# 5min_DIP.net
KiCad netlist of a schematic drawn in Altium Designer
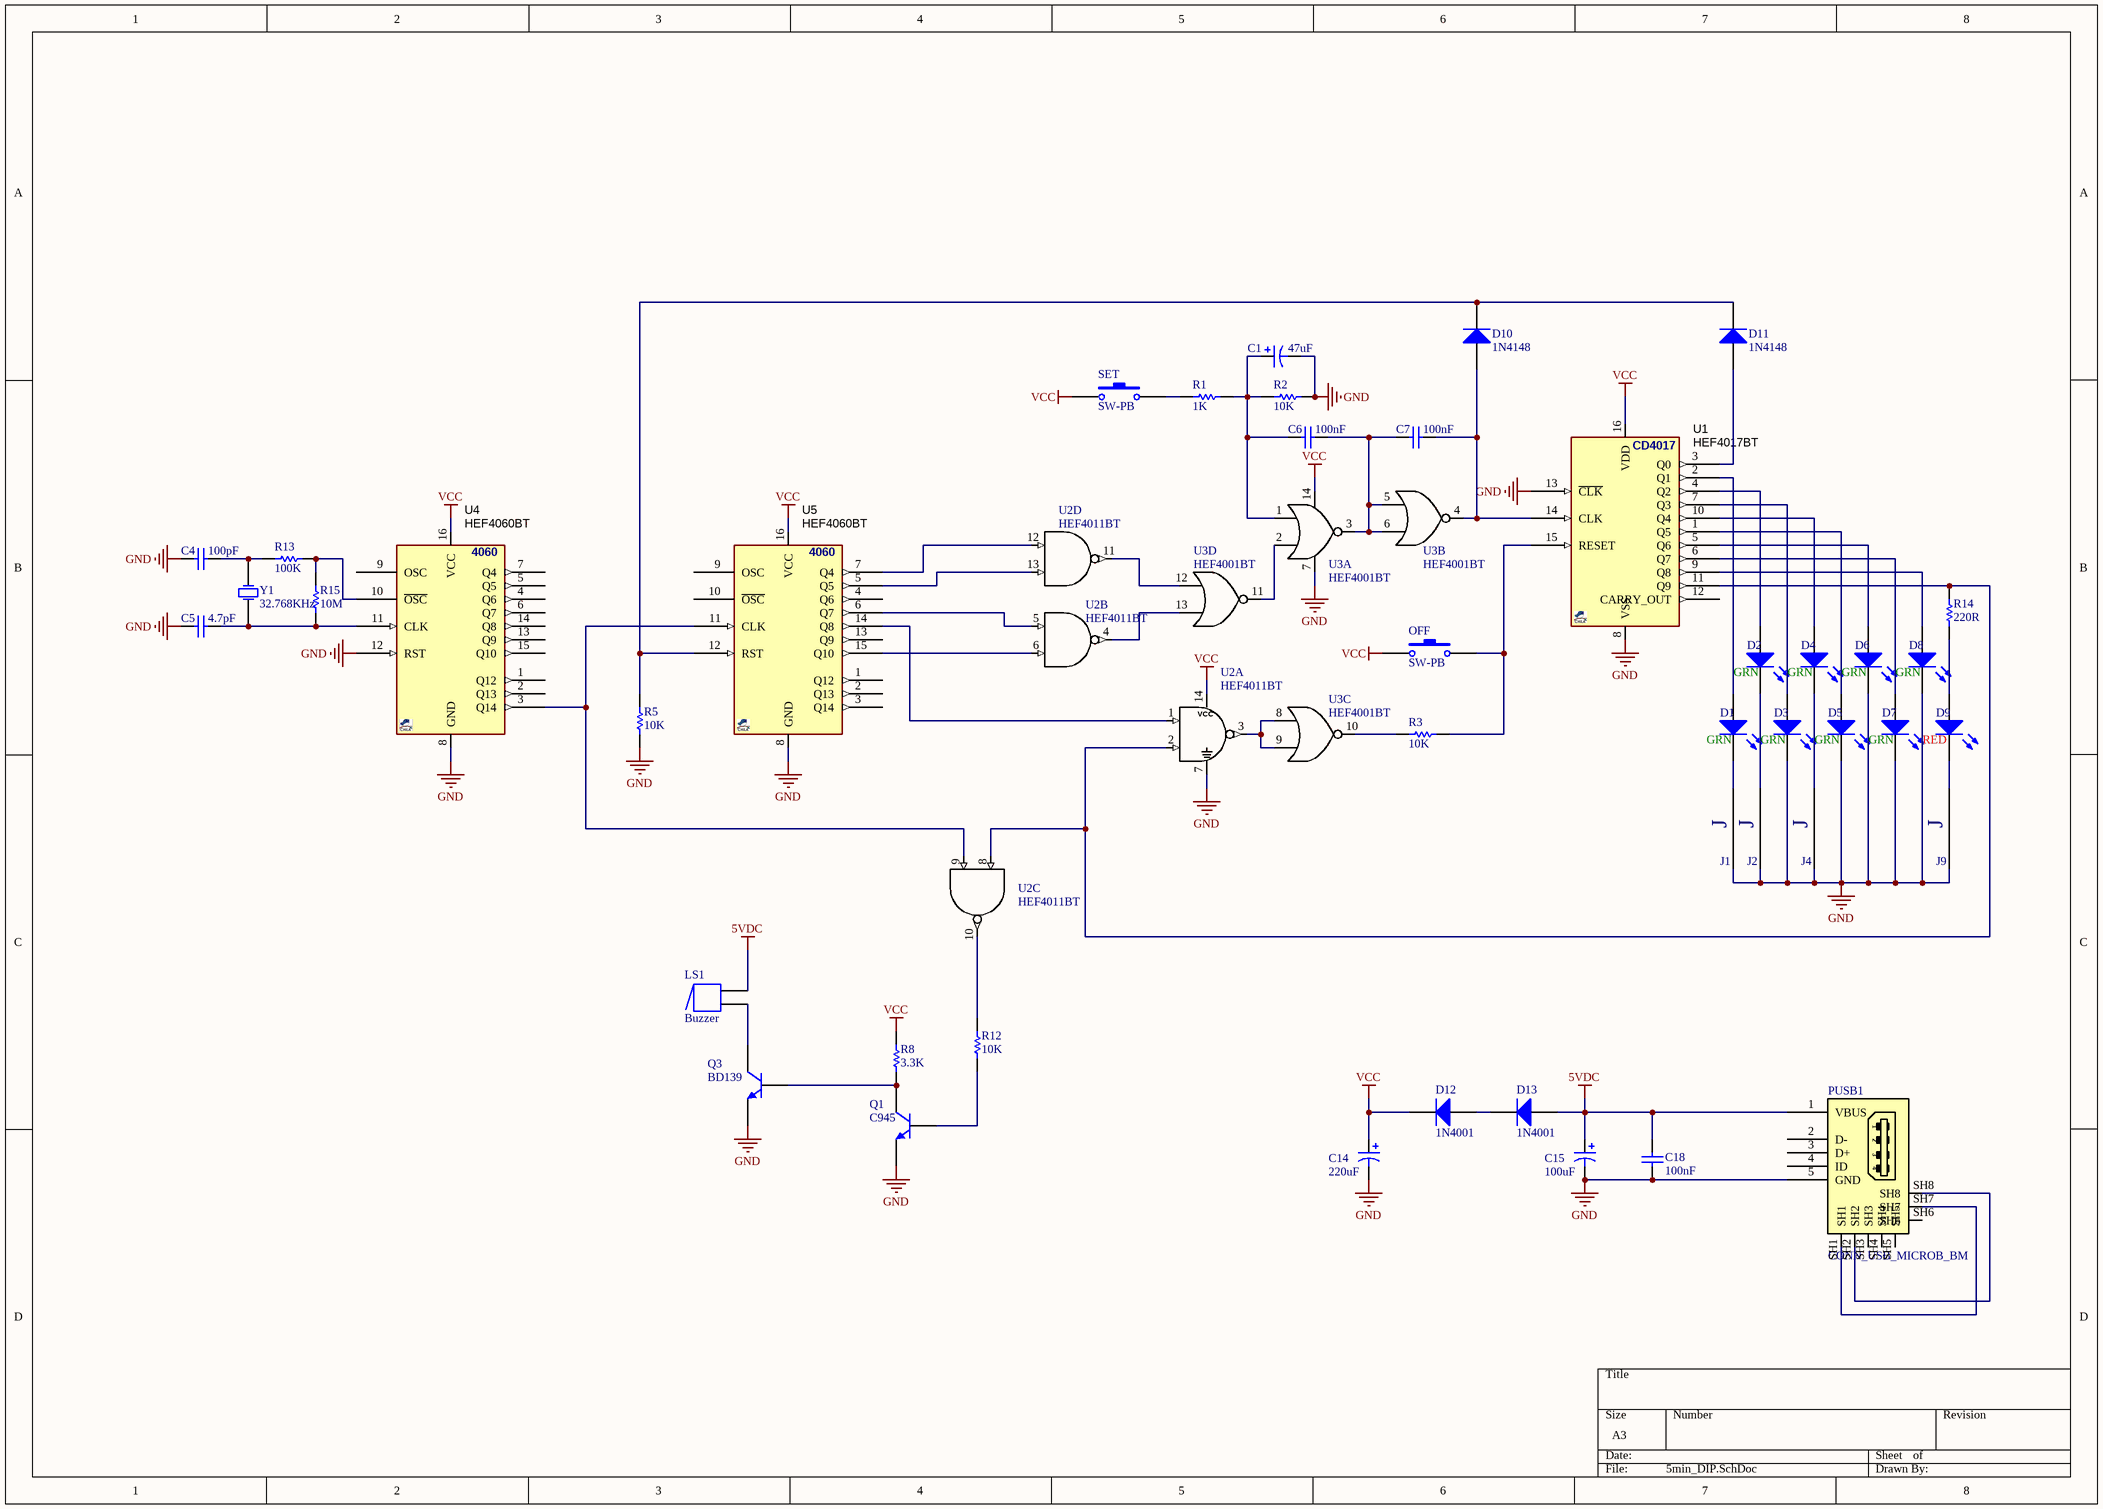
[diagram p0: 5min_DIP.SchDoc]

(export (version "E")
  (design (tool "Eeschema 10.0.6"))
  (components
    (comp (ref "C1")
      (value "47uF")
      (footprint "A")
      (description "Polarized Capacitor (Radial)")
      (fields (field (name "Comment") "Cap Pol1") (field (name "PUBLISHER") "Altium Limited"))
      (libsource (lib "Miscellaneous Devices") (part "Cap Pol1"))
    )
    (comp (ref "C4")
      (value "100pF")
      (footprint "CAP100N")
      (description "Capacitor")
      (fields (field (name "Comment") "Cap") (field (name "PUBLISHER") "Altium Limited"))
      (libsource (lib "Miscellaneous Devices") (part "Cap"))
    )
    (comp (ref "C5")
      (value "4.7pF")
      (footprint "CAP100N")
      (description "Capacitor")
      (fields (field (name "Comment") "Cap") (field (name "PUBLISHER") "Altium Limited"))
      (libsource (lib "Miscellaneous Devices") (part "Cap"))
    )
    (comp (ref "C6")
      (value "100nF")
      (footprint "CAP100N")
      (description "Capacitor")
      (fields (field (name "Comment") "Cap") (field (name "PUBLISHER") "Altium Limited"))
      (libsource (lib "Miscellaneous Devices") (part "Cap"))
    )
    (comp (ref "C7")
      (value "100nF")
      (footprint "CAP100N")
      (description "Capacitor")
      (fields (field (name "Comment") "Cap") (field (name "PUBLISHER") "Altium Limited"))
      (libsource (lib "Miscellaneous Devices") (part "Cap"))
    )
    (comp (ref "C14")
      (value "220uF")
      (footprint "A")
      (description "Polarized Capacitor (Radial)")
      (fields (field (name "Comment") "Cap Pol1") (field (name "PUBLISHER") "Altium Limited"))
      (libsource (lib "Miscellaneous Devices") (part "Cap Pol1"))
    )
    (comp (ref "C15")
      (value "100uF")
      (footprint "A")
      (description "Polarized Capacitor (Radial)")
      (fields (field (name "Comment") "Cap Pol1") (field (name "PUBLISHER") "Altium Limited"))
      (libsource (lib "Miscellaneous Devices") (part "Cap Pol1"))
    )
    (comp (ref "C18")
      (value "100nF")
      (footprint "CAP100N")
      (description "Capacitor")
      (fields (field (name "Comment") "Cap") (field (name "PUBLISHER") "Altium Limited"))
      (libsource (lib "Miscellaneous Devices") (part "Cap"))
    )
    (comp (ref "D1")
      (value "GRN")
      (footprint "LED3MM")
      (description "Typical INFRARED GaAs LED")
      (fields (field (name "PUBLISHER") "Altium Limited"))
      (libsource (lib "Miscellaneous Devices") (part "LED0"))
    )
    (comp (ref "D2")
      (value "GRN")
      (footprint "LED3MM")
      (description "Typical INFRARED GaAs LED")
      (fields (field (name "PUBLISHER") "Altium Limited"))
      (libsource (lib "Miscellaneous Devices") (part "LED0"))
    )
    (comp (ref "D3")
      (value "GRN")
      (footprint "LED3MM")
      (description "Typical INFRARED GaAs LED")
      (fields (field (name "PUBLISHER") "Altium Limited"))
      (libsource (lib "Miscellaneous Devices") (part "LED0"))
    )
    (comp (ref "D4")
      (value "GRN")
      (footprint "LED3MM")
      (description "Typical INFRARED GaAs LED")
      (fields (field (name "PUBLISHER") "Altium Limited"))
      (libsource (lib "Miscellaneous Devices") (part "LED0"))
    )
    (comp (ref "D5")
      (value "GRN")
      (footprint "LED3MM")
      (description "Typical INFRARED GaAs LED")
      (fields (field (name "PUBLISHER") "Altium Limited"))
      (libsource (lib "Miscellaneous Devices") (part "LED0"))
    )
    (comp (ref "D6")
      (value "GRN")
      (footprint "LED3MM")
      (description "Typical INFRARED GaAs LED")
      (fields (field (name "PUBLISHER") "Altium Limited"))
      (libsource (lib "Miscellaneous Devices") (part "LED0"))
    )
    (comp (ref "D7")
      (value "GRN")
      (footprint "LED3MM")
      (description "Typical INFRARED GaAs LED")
      (fields (field (name "PUBLISHER") "Altium Limited"))
      (libsource (lib "Miscellaneous Devices") (part "LED0"))
    )
    (comp (ref "D8")
      (value "GRN")
      (footprint "LED3MM")
      (description "Typical INFRARED GaAs LED")
      (fields (field (name "PUBLISHER") "Altium Limited"))
      (libsource (lib "Miscellaneous Devices") (part "LED0"))
    )
    (comp (ref "D9")
      (value "RED")
      (footprint "LED3MM")
      (description "Typical INFRARED GaAs LED")
      (fields (field (name "PUBLISHER") "Altium Limited"))
      (libsource (lib "Miscellaneous Devices") (part "LED0"))
    )
    (comp (ref "D10")
      (value "1N4148")
      (footprint "D_LN")
      (description "High Conductance Fast Diode")
      (fields (field (name "PUBLISHER") "Altium Limited"))
      (libsource (lib "Miscellaneous Devices") (part "Diode 1N4148"))
    )
    (comp (ref "D11")
      (value "1N4148")
      (footprint "D_LN")
      (description "High Conductance Fast Diode")
      (fields (field (name "PUBLISHER") "Altium Limited"))
      (libsource (lib "Miscellaneous Devices") (part "Diode 1N4148"))
    )
    (comp (ref "D12")
      (value "1N4001")
      (footprint "DO-35")
      (description "High Conductance Fast Diode")
      (fields (field (name "PUBLISHER") "Altium Limited"))
      (libsource (lib "Miscellaneous Devices") (part "Diode 1N4148"))
    )
    (comp (ref "D13")
      (value "1N4001")
      (footprint "DO-35")
      (description "High Conductance Fast Diode")
      (fields (field (name "PUBLISHER") "Altium Limited"))
      (libsource (lib "Miscellaneous Devices") (part "Diode 1N4148"))
    )
    (comp (ref "J1") (value "Jumper") (footprint "JMP") (libsource (lib "Schlib1") (part "Jumper")))
    (comp (ref "J2") (value "Jumper") (footprint "JMP") (libsource (lib "Schlib1") (part "Jumper")))
    (comp (ref "J4") (value "Jumper") (footprint "JMP") (libsource (lib "Schlib1") (part "Jumper")))
    (comp (ref "J9") (value "Jumper") (footprint "JMP") (libsource (lib "Schlib1") (part "Jumper")))
    (comp (ref "LS1")
      (value "Buzzer")
      (footprint "ABSM-1574")
      (description "Magnetic Transducer Buzzer")
      (fields (field (name "PUBLISHER") "Altium Limited"))
      (libsource (lib "Miscellaneous Devices") (part "Buzzer"))
    )
    (comp (ref "OFF")
      (value "SW-PB")
      (footprint "BUTTN")
      (description "Switch")
      (fields (field (name "PUBLISHER") "Altium Limited"))
      (libsource (lib "Miscellaneous Devices") (part "SW-PB"))
    )
    (comp (ref "PUSB1")
      (value "CONN_USB_MICROB_BM")
      (footprint "USB_MICRO_AB_BM_SHS")
      (description "CONN, USB, MICRO AB, R/A, SMD, BOTTOM MOUNT")
      (fields (field (name "MANF_P#") "1981584-1") (field (name "MANF") "TE"))
      (libsource (lib "conn_usb") (part "CONN_USB_MICRO_AB_BM_SHS"))
    )
    (comp (ref "Q1")
      (value "C945")
      (footprint "TO-92")
      (description "NPN Bipolar Transistor")
      (fields (field (name "PUBLISHER") "Altium Limited"))
      (libsource (lib "Miscellaneous Devices") (part "NPN"))
    )
    (comp (ref "Q3")
      (value "BD139")
      (footprint "BD139")
      (description "NPN Bipolar Transistor")
      (fields (field (name "PUBLISHER") "Altium Limited"))
      (libsource (lib "Miscellaneous Devices") (part "NPN"))
    )
    (comp (ref "R1")
      (value "1K")
      (footprint "AXIAL-0.3")
      (description "Resistor")
      (fields (field (name "Comment") "Res1") (field (name "PUBLISHER") "Altium Limited"))
      (libsource (lib "Miscellaneous Devices") (part "Res1"))
    )
    (comp (ref "R2")
      (value "10K")
      (footprint "AXIAL-0.3")
      (description "Resistor")
      (fields (field (name "Comment") "Res1") (field (name "PUBLISHER") "Altium Limited"))
      (libsource (lib "Miscellaneous Devices") (part "Res1"))
    )
    (comp (ref "R3")
      (value "10K")
      (footprint "AXIAL-0.3")
      (description "Resistor")
      (fields (field (name "Comment") "Res1") (field (name "PUBLISHER") "Altium Limited"))
      (libsource (lib "Miscellaneous Devices") (part "Res1"))
    )
    (comp (ref "R5")
      (value "10K")
      (footprint "AXIAL-0.3")
      (description "Resistor")
      (fields (field (name "Comment") "Res1") (field (name "PUBLISHER") "Altium Limited"))
      (libsource (lib "Miscellaneous Devices") (part "Res1"))
    )
    (comp (ref "R8")
      (value "3.3K")
      (footprint "AXIAL-0.3")
      (description "Resistor")
      (fields (field (name "Comment") "Res1") (field (name "PUBLISHER") "Altium Limited"))
      (libsource (lib "Miscellaneous Devices") (part "Res1"))
    )
    (comp (ref "R12")
      (value "10K")
      (footprint "AXIAL-0.3")
      (description "Resistor")
      (fields (field (name "Comment") "Res1") (field (name "PUBLISHER") "Altium Limited"))
      (libsource (lib "Miscellaneous Devices") (part "Res1"))
    )
    (comp (ref "R13")
      (value "100K")
      (footprint "AXIAL-0.3")
      (description "Resistor")
      (fields (field (name "Comment") "Res1") (field (name "PUBLISHER") "Altium Limited"))
      (libsource (lib "Miscellaneous Devices") (part "Res1"))
    )
    (comp (ref "R14")
      (value "220R")
      (footprint "AXIAL-0.3")
      (description "Resistor")
      (fields (field (name "Comment") "Res1") (field (name "PUBLISHER") "Altium Limited"))
      (libsource (lib "Miscellaneous Devices") (part "Res1"))
    )
    (comp (ref "R15")
      (value "10M")
      (footprint "AXIAL-0.3")
      (description "Resistor")
      (fields (field (name "Comment") "Res1") (field (name "PUBLISHER") "Altium Limited"))
      (libsource (lib "Miscellaneous Devices") (part "Res1"))
    )
    (comp (ref "SET")
      (value "SW-PB")
      (footprint "BUTTN")
      (description "Switch")
      (fields (field (name "PUBLISHER") "Altium Limited"))
      (libsource (lib "Miscellaneous Devices") (part "SW-PB"))
    )
    (comp (ref "U1")
      (value "HEF4017BT")
      (footprint "DIP_16")
      (description "Counter, 10 decoded output")
      (fields (field (name "MANF") "TI") (field (name "MANF_P#") "CD4017BE"))
      (libsource (lib "logic_counter") (part "CD4017_DIP16"))
    )
    (comp (ref "U2")
      (value "HEF4011BT")
      (footprint "DIP_14")
      (description "GATE, NAND, Quad 2-Input")
      (fields (field (name "MANF_P#") "CD4011BCMA"))
      (libsource (lib "logic_gate") (part "NANDx4_CD4011BCM"))
    )
    (comp (ref "U3")
      (value "HEF4001BT")
      (footprint "DIP_14")
      (description "Gate, NOR, Quad 2 Input")
      (fields (field (name "MANF") "Texas Instruments") (field (name "MANF_P#") "CD74HC02E"))
      (libsource (lib "KitchenTimerBoard") (part "NORx4_CD74HC02_DIP"))
    )
    (comp (ref "U4")
      (value "HEF4060BT")
      (footprint "DIP_16")
      (description "Counter, 14-Bit Binary, 3~18v, 10mA")
      (fields (field (name "MANF") "TI") (field (name "MANF_P#") "CD4060BE"))
      (libsource (lib "logic_counter") (part "CD4060_DIP16"))
    )
    (comp (ref "U5")
      (value "HEF4060BT")
      (footprint "DIP_16")
      (description "Counter, 14-Bit Binary, 3~18v, 10mA")
      (fields (field (name "MANF") "TI") (field (name "MANF_P#") "CD4060BE"))
      (libsource (lib "logic_counter") (part "CD4060_DIP16"))
    )
    (comp (ref "Y1")
      (value "32.768KHz")
      (footprint "XTAL")
      (description "Crystal Oscillator")
      (fields (field (name "Comment") "ECS-040-20-4X-DU") (field (name "PUBLISHER") "Altium Limited"))
      (libsource (lib "AXC-WS1") (part "XTAL"))
    )
  )
  (nets
    (net (code "1") (name "5VDC") (class "Default")
      (node (ref "C15") (pin "1") (pinfunction "1_1") (pintype "passive"))
      (node (ref "C18") (pin "2") (pinfunction "2_2") (pintype "passive"))
      (node (ref "D13") (pin "1") (pinfunction "A_1") (pintype "passive"))
      (node (ref "LS1") (pin "1") (pinfunction "1_1") (pintype "passive"))
      (node (ref "PUSB1") (pin "1") (pinfunction "VBUS_1") (pintype "power_in"))
    )
    (net (code "2") (name "GND") (class "Default")
      (node (ref "C1") (pin "2") (pinfunction "2_2") (pintype "passive"))
      (node (ref "C14") (pin "2") (pinfunction "2_2") (pintype "passive"))
      (node (ref "C15") (pin "2") (pinfunction "2_2") (pintype "passive"))
      (node (ref "C18") (pin "1") (pinfunction "1_1") (pintype "passive"))
      (node (ref "C4") (pin "1") (pinfunction "1_1") (pintype "passive"))
      (node (ref "C5") (pin "1") (pinfunction "1_1") (pintype "passive"))
      (node (ref "D3") (pin "2") (pinfunction "K_2") (pintype "passive"))
      (node (ref "D5") (pin "2") (pinfunction "K_2") (pintype "passive"))
      (node (ref "D6") (pin "2") (pinfunction "K_2") (pintype "passive"))
      (node (ref "D7") (pin "2") (pinfunction "K_2") (pintype "passive"))
      (node (ref "D8") (pin "2") (pinfunction "K_2") (pintype "passive"))
      (node (ref "J1") (pin "1") (pinfunction "1_1") (pintype "passive"))
      (node (ref "J2") (pin "1") (pinfunction "1_1") (pintype "passive"))
      (node (ref "J4") (pin "1") (pinfunction "1_1") (pintype "passive"))
      (node (ref "J9") (pin "1") (pinfunction "1_1") (pintype "passive"))
      (node (ref "PUSB1") (pin "5") (pinfunction "GND_5") (pintype "power_in"))
      (node (ref "Q1") (pin "3") (pinfunction "E_3") (pintype "passive"))
      (node (ref "Q3") (pin "3") (pinfunction "E_3") (pintype "passive"))
      (node (ref "R2") (pin "2") (pinfunction "2_2") (pintype "passive"))
      (node (ref "R5") (pin "2") (pinfunction "2_2") (pintype "passive"))
      (node (ref "U1") (pin "13") (pinfunction "~{CLK}_13") (pintype "input"))
      (node (ref "U1") (pin "8") (pinfunction "VSS_8") (pintype "power_in"))
      (node (ref "U2") (pin "7") (pinfunction "GND_7") (pintype "power_in"))
      (node (ref "U3") (pin "7") (pinfunction "GND_7") (pintype "passive"))
      (node (ref "U4") (pin "12") (pinfunction "RST_12") (pintype "input"))
      (node (ref "U4") (pin "8") (pinfunction "GND_8") (pintype "power_in"))
      (node (ref "U5") (pin "8") (pinfunction "GND_8") (pintype "power_in"))
    )
    (net (code "3") (name "Net-(C1-Pad1)") (class "Default")
      (node (ref "C1") (pin "1") (pinfunction "1_1") (pintype "passive"))
      (node (ref "C6") (pin "1") (pinfunction "1_1") (pintype "passive"))
      (node (ref "R1") (pin "2") (pinfunction "2_2") (pintype "passive"))
      (node (ref "R2") (pin "1") (pinfunction "1_1") (pintype "passive"))
      (node (ref "U3") (pin "1") (pinfunction "1_1") (pintype "passive"))
    )
    (net (code "4") (name "Net-(C6-Pad2)") (class "Default")
      (node (ref "C6") (pin "2") (pinfunction "2_2") (pintype "passive"))
      (node (ref "C7") (pin "1") (pinfunction "1_1") (pintype "passive"))
      (node (ref "U3") (pin "3") (pinfunction "3_3") (pintype "passive"))
      (node (ref "U3") (pin "5") (pinfunction "5_5") (pintype "passive"))
      (node (ref "U3") (pin "6") (pinfunction "6_6") (pintype "passive"))
    )
    (net (code "5") (name "Net-(D1-A)") (class "Default")
      (node (ref "D1") (pin "1") (pinfunction "A_1") (pintype "passive"))
      (node (ref "U1") (pin "2") (pinfunction "Q1_2") (pintype "output"))
    )
    (net (code "6") (name "Net-(D1-K)") (class "Default")
      (node (ref "D1") (pin "2") (pinfunction "K_2") (pintype "passive"))
      (node (ref "J1") (pin "2") (pinfunction "2_2") (pintype "passive"))
    )
    (net (code "7") (name "Net-(D2-A)") (class "Default")
      (node (ref "D2") (pin "1") (pinfunction "A_1") (pintype "passive"))
      (node (ref "U1") (pin "4") (pinfunction "Q2_4") (pintype "output"))
    )
    (net (code "8") (name "Net-(D2-K)") (class "Default")
      (node (ref "D2") (pin "2") (pinfunction "K_2") (pintype "passive"))
      (node (ref "J2") (pin "2") (pinfunction "2_2") (pintype "passive"))
    )
    (net (code "9") (name "Net-(D3-A)") (class "Default")
      (node (ref "D3") (pin "1") (pinfunction "A_1") (pintype "passive"))
      (node (ref "U1") (pin "7") (pinfunction "Q3_7") (pintype "output"))
    )
    (net (code "10") (name "Net-(D4-A)") (class "Default")
      (node (ref "D4") (pin "1") (pinfunction "A_1") (pintype "passive"))
      (node (ref "U1") (pin "10") (pinfunction "Q4_10") (pintype "output"))
    )
    (net (code "11") (name "Net-(D4-K)") (class "Default")
      (node (ref "D4") (pin "2") (pinfunction "K_2") (pintype "passive"))
      (node (ref "J4") (pin "2") (pinfunction "2_2") (pintype "passive"))
    )
    (net (code "12") (name "Net-(D5-A)") (class "Default")
      (node (ref "D5") (pin "1") (pinfunction "A_1") (pintype "passive"))
      (node (ref "U1") (pin "1") (pinfunction "Q5_1") (pintype "output"))
    )
    (net (code "13") (name "Net-(D6-A)") (class "Default")
      (node (ref "D6") (pin "1") (pinfunction "A_1") (pintype "passive"))
      (node (ref "U1") (pin "5") (pinfunction "Q6_5") (pintype "output"))
    )
    (net (code "14") (name "Net-(D7-A)") (class "Default")
      (node (ref "D7") (pin "1") (pinfunction "A_1") (pintype "passive"))
      (node (ref "U1") (pin "6") (pinfunction "Q7_6") (pintype "output"))
    )
    (net (code "15") (name "Net-(D8-A)") (class "Default")
      (node (ref "D8") (pin "1") (pinfunction "A_1") (pintype "passive"))
      (node (ref "U1") (pin "9") (pinfunction "Q8_9") (pintype "output"))
    )
    (net (code "16") (name "Net-(D9-A)") (class "Default")
      (node (ref "D9") (pin "1") (pinfunction "A_1") (pintype "passive"))
      (node (ref "R14") (pin "1") (pinfunction "1_1") (pintype "passive"))
    )
    (net (code "17") (name "Net-(D9-K)") (class "Default")
      (node (ref "D9") (pin "2") (pinfunction "K_2") (pintype "passive"))
      (node (ref "J9") (pin "2") (pinfunction "2_2") (pintype "passive"))
    )
    (net (code "18") (name "Net-(D10-A)") (class "Default")
      (node (ref "C7") (pin "2") (pinfunction "2_2") (pintype "passive"))
      (node (ref "D10") (pin "1") (pinfunction "A_1") (pintype "passive"))
      (node (ref "U1") (pin "14") (pinfunction "CLK_14") (pintype "input"))
      (node (ref "U3") (pin "4") (pinfunction "4_4") (pintype "passive"))
    )
    (net (code "19") (name "Net-(D10-K)") (class "Default")
      (node (ref "D10") (pin "2") (pinfunction "K_2") (pintype "passive"))
      (node (ref "D11") (pin "2") (pinfunction "K_2") (pintype "passive"))
      (node (ref "R5") (pin "1") (pinfunction "1_1") (pintype "passive"))
      (node (ref "U5") (pin "12") (pinfunction "RST_12") (pintype "input"))
    )
    (net (code "20") (name "Net-(D11-A)") (class "Default")
      (node (ref "D11") (pin "1") (pinfunction "A_1") (pintype "passive"))
      (node (ref "U1") (pin "3") (pinfunction "Q0_3") (pintype "output"))
    )
    (net (code "21") (name "Net-(D12-A)") (class "Default")
      (node (ref "D12") (pin "1") (pinfunction "A_1") (pintype "passive"))
      (node (ref "D13") (pin "2") (pinfunction "K_2") (pintype "passive"))
    )
    (net (code "22") (name "Net-(PUSB1-PadSH1)") (class "Default")
      (node (ref "PUSB1") (pin "SH1") (pinfunction "SH1_SH1") (pintype "passive"))
      (node (ref "PUSB1") (pin "SH7") (pinfunction "SH7_SH7") (pintype "passive"))
    )
    (net (code "23") (name "Net-(PUSB1-PadSH2)") (class "Default")
      (node (ref "PUSB1") (pin "SH2") (pinfunction "SH2_SH2") (pintype "passive"))
      (node (ref "PUSB1") (pin "SH8") (pinfunction "SH8_SH8") (pintype "passive"))
    )
    (net (code "24") (name "Net-(Q1-B)") (class "Default")
      (node (ref "Q1") (pin "2") (pinfunction "B_2") (pintype "passive"))
      (node (ref "R12") (pin "2") (pinfunction "2_2") (pintype "passive"))
    )
    (net (code "25") (name "Net-(Q1-C)") (class "Default")
      (node (ref "Q1") (pin "1") (pinfunction "C_1") (pintype "passive"))
      (node (ref "Q3") (pin "2") (pinfunction "B_2") (pintype "passive"))
      (node (ref "R8") (pin "1") (pinfunction "1_1") (pintype "passive"))
    )
    (net (code "26") (name "Net-(Q3-C)") (class "Default")
      (node (ref "LS1") (pin "2") (pinfunction "2_2") (pintype "passive"))
      (node (ref "Q3") (pin "1") (pinfunction "C_1") (pintype "passive"))
    )
    (net (code "27") (name "Net-(R1-Pad1)") (class "Default")
      (node (ref "R1") (pin "1") (pinfunction "1_1") (pintype "passive"))
      (node (ref "SET") (pin "1") (pinfunction "1_1") (pintype "passive"))
    )
    (net (code "28") (name "Net-(R3-Pad1)") (class "Default")
      (node (ref "R3") (pin "1") (pinfunction "1_1") (pintype "passive"))
      (node (ref "U3") (pin "10") (pinfunction "10_10") (pintype "passive"))
    )
    (net (code "29") (name "Net-(U1-Q9)") (class "Default")
      (node (ref "R14") (pin "2") (pinfunction "2_2") (pintype "passive"))
      (node (ref "U1") (pin "11") (pinfunction "Q9_11") (pintype "output"))
      (node (ref "U2") (pin "2") (pinfunction "B_2") (pintype "input"))
      (node (ref "U2") (pin "8") (pinfunction "A_8") (pintype "input"))
    )
    (net (code "30") (name "Net-(U1-RESET)") (class "Default")
      (node (ref "OFF") (pin "2") (pinfunction "2_2") (pintype "passive"))
      (node (ref "R3") (pin "2") (pinfunction "2_2") (pintype "passive"))
      (node (ref "U1") (pin "15") (pinfunction "RESET_15") (pintype "input"))
    )
    (net (code "31") (name "Net-(U2A-A)") (class "Default")
      (node (ref "U2") (pin "1") (pinfunction "A_1") (pintype "input"))
      (node (ref "U5") (pin "14") (pinfunction "Q8_14") (pintype "output"))
    )
    (net (code "32") (name "Net-(U2A-J)") (class "Default")
      (node (ref "U2") (pin "3") (pinfunction "J_3") (pintype "output"))
      (node (ref "U3") (pin "8") (pinfunction "8_8") (pintype "passive"))
      (node (ref "U3") (pin "9") (pinfunction "9_9") (pintype "passive"))
    )
    (net (code "33") (name "Net-(U2B-A)") (class "Default")
      (node (ref "U2") (pin "5") (pinfunction "A_5") (pintype "input"))
      (node (ref "U5") (pin "6") (pinfunction "Q7_6") (pintype "output"))
    )
    (net (code "34") (name "Net-(U2B-B)") (class "Default")
      (node (ref "U2") (pin "6") (pinfunction "B_6") (pintype "input"))
      (node (ref "U5") (pin "15") (pinfunction "Q10_15") (pintype "output"))
    )
    (net (code "35") (name "Net-(U2B-J)") (class "Default")
      (node (ref "U2") (pin "4") (pinfunction "J_4") (pintype "output"))
      (node (ref "U3") (pin "13") (pinfunction "13_13") (pintype "passive"))
    )
    (net (code "36") (name "Net-(U2C-F)") (class "Default")
      (node (ref "U2") (pin "9") (pinfunction "F_9") (pintype "input"))
      (node (ref "U4") (pin "3") (pinfunction "Q14_3") (pintype "output"))
      (node (ref "U5") (pin "11") (pinfunction "CLK_11") (pintype "input"))
    )
    (net (code "37") (name "Net-(U2C-J)") (class "Default")
      (node (ref "R12") (pin "1") (pinfunction "1_1") (pintype "passive"))
      (node (ref "U2") (pin "10") (pinfunction "J_10") (pintype "output"))
    )
    (net (code "38") (name "Net-(U2D-A)") (class "Default")
      (node (ref "U2") (pin "12") (pinfunction "A_12") (pintype "input"))
      (node (ref "U5") (pin "7") (pinfunction "Q4_7") (pintype "output"))
    )
    (net (code "39") (name "Net-(U2D-B)") (class "Default")
      (node (ref "U2") (pin "13") (pinfunction "B_13") (pintype "input"))
      (node (ref "U5") (pin "5") (pinfunction "Q5_5") (pintype "output"))
    )
    (net (code "40") (name "Net-(U2D-J)") (class "Default")
      (node (ref "U2") (pin "11") (pinfunction "J_11") (pintype "output"))
      (node (ref "U3") (pin "12") (pinfunction "12_12") (pintype "passive"))
    )
    (net (code "41") (name "Net-(U3-Pad11)") (class "Default")
      (node (ref "U3") (pin "11") (pinfunction "11_11") (pintype "passive"))
      (node (ref "U3") (pin "2") (pinfunction "2_2") (pintype "passive"))
    )
    (net (code "42") (name "Net-(U4-CLK)") (class "Default")
      (node (ref "C5") (pin "2") (pinfunction "2_2") (pintype "passive"))
      (node (ref "R15") (pin "1") (pinfunction "1_1") (pintype "passive"))
      (node (ref "U4") (pin "11") (pinfunction "CLK_11") (pintype "input"))
      (node (ref "Y1") (pin "2") (pinfunction "OSC2_2") (pintype "passive"))
    )
    (net (code "43") (name "Net-(U4-~{OSC})") (class "Default")
      (node (ref "R13") (pin "2") (pinfunction "2_2") (pintype "passive"))
      (node (ref "R15") (pin "2") (pinfunction "2_2") (pintype "passive"))
      (node (ref "U4") (pin "10") (pinfunction "~{OSC}_10") (pintype "passive"))
    )
    (net (code "44") (name "Net-(Y1-OSC1)") (class "Default")
      (node (ref "C4") (pin "2") (pinfunction "2_2") (pintype "passive"))
      (node (ref "R13") (pin "1") (pinfunction "1_1") (pintype "passive"))
      (node (ref "Y1") (pin "1") (pinfunction "OSC1_1") (pintype "passive"))
    )
    (net (code "45") (name "VCC") (class "Default")
      (node (ref "C14") (pin "1") (pinfunction "1_1") (pintype "passive"))
      (node (ref "D12") (pin "2") (pinfunction "K_2") (pintype "passive"))
      (node (ref "OFF") (pin "1") (pinfunction "1_1") (pintype "passive"))
      (node (ref "R8") (pin "2") (pinfunction "2_2") (pintype "passive"))
      (node (ref "SET") (pin "2") (pinfunction "2_2") (pintype "passive"))
      (node (ref "U1") (pin "16") (pinfunction "VDD_16") (pintype "power_in"))
      (node (ref "U2") (pin "14") (pinfunction "VDD_14") (pintype "power_in"))
      (node (ref "U3") (pin "14") (pinfunction "VCC_14") (pintype "passive"))
      (node (ref "U4") (pin "16") (pinfunction "VCC_16") (pintype "power_in"))
      (node (ref "U5") (pin "16") (pinfunction "VCC_16") (pintype "power_in"))
    )
    (net (code "46") (name "unconnected-(PUSB1-D+-Pad3)") (class "Default")
      (node (ref "PUSB1") (pin "3") (pinfunction "D+_3") (pintype "passive"))
    )
    (net (code "47") (name "unconnected-(PUSB1-D--Pad2)") (class "Default")
      (node (ref "PUSB1") (pin "2") (pinfunction "D-_2") (pintype "passive"))
    )
    (net (code "48") (name "unconnected-(PUSB1-ID-Pad4)") (class "Default")
      (node (ref "PUSB1") (pin "4") (pinfunction "ID_4") (pintype "power_in"))
    )
    (net (code "49") (name "unconnected-(PUSB1-PadSH3)") (class "Default")
      (node (ref "PUSB1") (pin "SH3") (pinfunction "SH3_SH3") (pintype "passive"))
    )
    (net (code "50") (name "unconnected-(PUSB1-PadSH4)") (class "Default")
      (node (ref "PUSB1") (pin "SH4") (pinfunction "SH4_SH4") (pintype "passive"))
    )
    (net (code "51") (name "unconnected-(PUSB1-PadSH5)") (class "Default")
      (node (ref "PUSB1") (pin "SH5") (pinfunction "SH5_SH5") (pintype "passive"))
    )
    (net (code "52") (name "unconnected-(PUSB1-PadSH6)") (class "Default")
      (node (ref "PUSB1") (pin "SH6") (pinfunction "SH6_SH6") (pintype "passive"))
    )
    (net (code "53") (name "unconnected-(U1-CARRY_OUT-Pad12)") (class "Default")
      (node (ref "U1") (pin "12") (pinfunction "CARRY_OUT_12") (pintype "output"))
    )
    (net (code "54") (name "unconnected-(U4-OSC-Pad9)") (class "Default")
      (node (ref "U4") (pin "9") (pinfunction "OSC_9") (pintype "passive"))
    )
    (net (code "55") (name "unconnected-(U4-Q4-Pad7)") (class "Default")
      (node (ref "U4") (pin "7") (pinfunction "Q4_7") (pintype "output"))
    )
    (net (code "56") (name "unconnected-(U4-Q5-Pad5)") (class "Default")
      (node (ref "U4") (pin "5") (pinfunction "Q5_5") (pintype "output"))
    )
    (net (code "57") (name "unconnected-(U4-Q6-Pad4)") (class "Default")
      (node (ref "U4") (pin "4") (pinfunction "Q6_4") (pintype "output"))
    )
    (net (code "58") (name "unconnected-(U4-Q7-Pad6)") (class "Default")
      (node (ref "U4") (pin "6") (pinfunction "Q7_6") (pintype "output"))
    )
    (net (code "59") (name "unconnected-(U4-Q8-Pad14)") (class "Default")
      (node (ref "U4") (pin "14") (pinfunction "Q8_14") (pintype "output"))
    )
    (net (code "60") (name "unconnected-(U4-Q9-Pad13)") (class "Default")
      (node (ref "U4") (pin "13") (pinfunction "Q9_13") (pintype "output"))
    )
    (net (code "61") (name "unconnected-(U4-Q10-Pad15)") (class "Default")
      (node (ref "U4") (pin "15") (pinfunction "Q10_15") (pintype "output"))
    )
    (net (code "62") (name "unconnected-(U4-Q12-Pad1)") (class "Default")
      (node (ref "U4") (pin "1") (pinfunction "Q12_1") (pintype "output"))
    )
    (net (code "63") (name "unconnected-(U4-Q13-Pad2)") (class "Default")
      (node (ref "U4") (pin "2") (pinfunction "Q13_2") (pintype "output"))
    )
    (net (code "64") (name "unconnected-(U5-OSC-Pad9)") (class "Default")
      (node (ref "U5") (pin "9") (pinfunction "OSC_9") (pintype "passive"))
    )
    (net (code "65") (name "unconnected-(U5-Q6-Pad4)") (class "Default")
      (node (ref "U5") (pin "4") (pinfunction "Q6_4") (pintype "output"))
    )
    (net (code "66") (name "unconnected-(U5-Q9-Pad13)") (class "Default")
      (node (ref "U5") (pin "13") (pinfunction "Q9_13") (pintype "output"))
    )
    (net (code "67") (name "unconnected-(U5-Q12-Pad1)") (class "Default")
      (node (ref "U5") (pin "1") (pinfunction "Q12_1") (pintype "output"))
    )
    (net (code "68") (name "unconnected-(U5-Q13-Pad2)") (class "Default")
      (node (ref "U5") (pin "2") (pinfunction "Q13_2") (pintype "output"))
    )
    (net (code "69") (name "unconnected-(U5-Q14-Pad3)") (class "Default")
      (node (ref "U5") (pin "3") (pinfunction "Q14_3") (pintype "output"))
    )
    (net (code "70") (name "unconnected-(U5-~{OSC}-Pad10)") (class "Default")
      (node (ref "U5") (pin "10") (pinfunction "~{OSC}_10") (pintype "passive"))
    )
  )
)
